# Sensors.net
KiCad netlist of a schematic drawn in Altium Designer
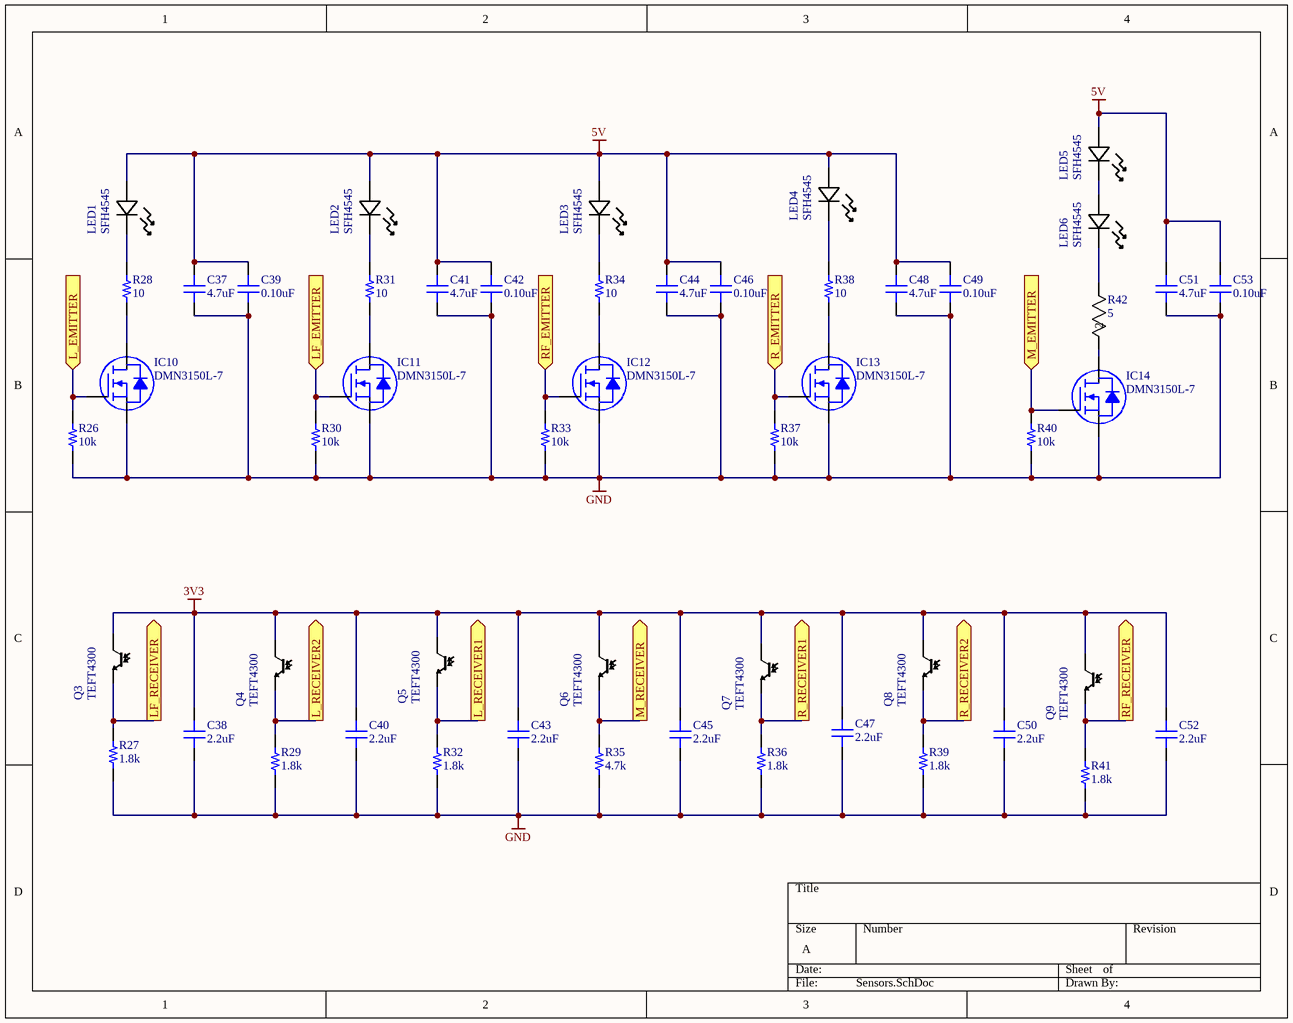
[diagram p0: Sensors.SchDoc]

(export (version "E")
  (design (tool "Eeschema 10.0.6"))
  (components
    (comp (ref "C37")
      (value "4.7uF")
      (footprint "CAP 0805/2012")
      (description "CAP CER 4.7UF 10V Y5V 0805")
      (fields (field (name "PART NUMBER") "CC0805ZRY5V6BB475") (field (name "MANUFACTURER") "Yageo"))
      (libsource (lib "Celestial Library Database") (part "Capacitor"))
    )
    (comp (ref "C38")
      (value "2.2uF")
      (footprint "CAP 0402/1005")
      (description "CAP CER 2.2UF 10V X5R 0402")
      (fields
        (field (name "PART NUMBER") "CL05A225KP5NSNC")
        (field (name "MANUFACTURER") "Samsung Electro-Mechanics America, Inc.")
      )
      (libsource (lib "Celestial Library Database") (part "Capacitor"))
    )
    (comp (ref "C39")
      (value "0.10uF")
      (footprint "CAP 0603/1608")
      (description "CAP CER 0.1UF 25V Y5V 0603")
      (fields (field (name "PART NUMBER") "CC0603ZRY5V8BB104") (field (name "MANUFACTURER") "Yageo"))
      (libsource (lib "Celestial Library Database") (part "Capacitor"))
    )
    (comp (ref "C40")
      (value "2.2uF")
      (footprint "CAP 0402/1005")
      (description "CAP CER 2.2UF 10V X5R 0402")
      (fields
        (field (name "PART NUMBER") "CL05A225KP5NSNC")
        (field (name "MANUFACTURER") "Samsung Electro-Mechanics America, Inc.")
      )
      (libsource (lib "Celestial Library Database") (part "Capacitor"))
    )
    (comp (ref "C41")
      (value "4.7uF")
      (footprint "CAP 0805/2012")
      (description "CAP CER 4.7UF 10V Y5V 0805")
      (fields (field (name "PART NUMBER") "CC0805ZRY5V6BB475") (field (name "MANUFACTURER") "Yageo"))
      (libsource (lib "Celestial Library Database") (part "Capacitor"))
    )
    (comp (ref "C42")
      (value "0.10uF")
      (footprint "CAP 0603/1608")
      (description "CAP CER 0.1UF 25V Y5V 0603")
      (fields (field (name "PART NUMBER") "CC0603ZRY5V8BB104") (field (name "MANUFACTURER") "Yageo"))
      (libsource (lib "Celestial Library Database") (part "Capacitor"))
    )
    (comp (ref "C43")
      (value "2.2uF")
      (footprint "CAP 0402/1005")
      (description "CAP CER 2.2UF 10V X5R 0402")
      (fields
        (field (name "PART NUMBER") "CL05A225KP5NSNC")
        (field (name "MANUFACTURER") "Samsung Electro-Mechanics America, Inc.")
      )
      (libsource (lib "Celestial Library Database") (part "Capacitor"))
    )
    (comp (ref "C44")
      (value "4.7uF")
      (footprint "CAP 0805/2012")
      (description "CAP CER 4.7UF 10V Y5V 0805")
      (fields (field (name "PART NUMBER") "CC0805ZRY5V6BB475") (field (name "MANUFACTURER") "Yageo"))
      (libsource (lib "Celestial Library Database") (part "Capacitor"))
    )
    (comp (ref "C45")
      (value "2.2uF")
      (footprint "CAP 0402/1005")
      (description "CAP CER 2.2UF 10V X5R 0402")
      (fields
        (field (name "PART NUMBER") "CL05A225KP5NSNC")
        (field (name "MANUFACTURER") "Samsung Electro-Mechanics America, Inc.")
      )
      (libsource (lib "Celestial Library Database") (part "Capacitor"))
    )
    (comp (ref "C46")
      (value "0.10uF")
      (footprint "CAP 0603/1608")
      (description "CAP CER 0.1UF 25V Y5V 0603")
      (fields (field (name "PART NUMBER") "CC0603ZRY5V8BB104") (field (name "MANUFACTURER") "Yageo"))
      (libsource (lib "Celestial Library Database") (part "Capacitor"))
    )
    (comp (ref "C47")
      (value "2.2uF")
      (footprint "CAP 0402/1005")
      (description "CAP CER 2.2UF 10V X5R 0402")
      (fields
        (field (name "PART NUMBER") "CL05A225KP5NSNC")
        (field (name "MANUFACTURER") "Samsung Electro-Mechanics America, Inc.")
      )
      (libsource (lib "Celestial Library Database") (part "Capacitor"))
    )
    (comp (ref "C48")
      (value "4.7uF")
      (footprint "CAP 0805/2012")
      (description "CAP CER 4.7UF 10V Y5V 0805")
      (fields (field (name "PART NUMBER") "CC0805ZRY5V6BB475") (field (name "MANUFACTURER") "Yageo"))
      (libsource (lib "Celestial Library Database") (part "Capacitor"))
    )
    (comp (ref "C49")
      (value "0.10uF")
      (footprint "CAP 0603/1608")
      (description "CAP CER 0.1UF 25V Y5V 0603")
      (fields (field (name "PART NUMBER") "CC0603ZRY5V8BB104") (field (name "MANUFACTURER") "Yageo"))
      (libsource (lib "Celestial Library Database") (part "Capacitor"))
    )
    (comp (ref "C50")
      (value "2.2uF")
      (footprint "CAP 0402/1005")
      (description "CAP CER 2.2UF 10V X5R 0402")
      (fields
        (field (name "PART NUMBER") "CL05A225KP5NSNC")
        (field (name "MANUFACTURER") "Samsung Electro-Mechanics America, Inc.")
      )
      (libsource (lib "Celestial Library Database") (part "Capacitor"))
    )
    (comp (ref "C51")
      (value "4.7uF")
      (footprint "CAP 0805/2012")
      (description "CAP CER 4.7UF 10V Y5V 0805")
      (fields (field (name "PART NUMBER") "CC0805ZRY5V6BB475") (field (name "MANUFACTURER") "Yageo"))
      (libsource (lib "Celestial Library Database") (part "Capacitor"))
    )
    (comp (ref "C52")
      (value "2.2uF")
      (footprint "CAP 0402/1005")
      (description "CAP CER 2.2UF 10V X5R 0402")
      (fields
        (field (name "PART NUMBER") "CL05A225KP5NSNC")
        (field (name "MANUFACTURER") "Samsung Electro-Mechanics America, Inc.")
      )
      (libsource (lib "Celestial Library Database") (part "Capacitor"))
    )
    (comp (ref "C53")
      (value "0.10uF")
      (footprint "CAP 0603/1608")
      (description "CAP CER 0.1UF 25V Y5V 0603")
      (fields (field (name "PART NUMBER") "CC0603ZRY5V8BB104") (field (name "MANUFACTURER") "Yageo"))
      (libsource (lib "Celestial Library Database") (part "Capacitor"))
    )
    (comp (ref "IC10")
      (value "DMN3150L-7")
      (footprint "DIODES SOT-23-3")
      (description "MOSFET N-CH 28V 3.2A SOT23-3")
      (fields (field (name "MANUFACTURER") "Diodes Incorporated"))
      (libsource (lib "Celestial Library Database") (part "DIODES INC MOSFET N-CH SOT-23-3"))
    )
    (comp (ref "IC11")
      (value "DMN3150L-7")
      (footprint "DIODES SOT-23-3")
      (description "MOSFET N-CH 28V 3.2A SOT23-3")
      (fields (field (name "MANUFACTURER") "Diodes Incorporated"))
      (libsource (lib "Celestial Library Database") (part "DIODES INC MOSFET N-CH SOT-23-3"))
    )
    (comp (ref "IC12")
      (value "DMN3150L-7")
      (footprint "DIODES SOT-23-3")
      (description "MOSFET N-CH 28V 3.2A SOT23-3")
      (fields (field (name "MANUFACTURER") "Diodes Incorporated"))
      (libsource (lib "Celestial Library Database") (part "DIODES INC MOSFET N-CH SOT-23-3"))
    )
    (comp (ref "IC13")
      (value "DMN3150L-7")
      (footprint "DIODES SOT-23-3")
      (description "MOSFET N-CH 28V 3.2A SOT23-3")
      (fields (field (name "MANUFACTURER") "Diodes Incorporated"))
      (libsource (lib "Celestial Library Database") (part "DIODES INC MOSFET N-CH SOT-23-3"))
    )
    (comp (ref "IC14")
      (value "DMN3150L-7")
      (footprint "DIODES SOT-23-3")
      (description "MOSFET N-CH 28V 3.2A SOT23-3")
      (fields (field (name "MANUFACTURER") "Diodes Incorporated"))
      (libsource (lib "Celestial Library Database") (part "DIODES INC MOSFET N-CH SOT-23-3"))
    )
    (comp (ref "LED1")
      (value "SFH4545")
      (footprint "LED_TLH")
      (description "Imported")
      (libsource (lib "AltiumDesigner") (part "SFH4545"))
    )
    (comp (ref "LED2")
      (value "SFH4545")
      (footprint "LED_TLH")
      (description "Imported")
      (libsource (lib "AltiumDesigner") (part "SFH4545"))
    )
    (comp (ref "LED3")
      (value "SFH4545")
      (footprint "LED_TLH")
      (description "Imported")
      (libsource (lib "AltiumDesigner") (part "SFH4545"))
    )
    (comp (ref "LED4")
      (value "SFH4545")
      (footprint "LED_TLH")
      (description "Imported")
      (libsource (lib "AltiumDesigner") (part "SFH4545"))
    )
    (comp (ref "LED5")
      (value "SFH4545")
      (footprint "LED_TLH")
      (description "Imported")
      (libsource (lib "AltiumDesigner") (part "SFH4545"))
    )
    (comp (ref "LED6")
      (value "SFH4545")
      (footprint "LED_TLH")
      (description "Imported")
      (libsource (lib "AltiumDesigner") (part "SFH4545"))
    )
    (comp (ref "Q3")
      (value "TEFT4300")
      (footprint "LED_TLH")
      (description "Imported")
      (libsource (lib "AltiumDesigner") (part "TEFT4300"))
    )
    (comp (ref "Q4")
      (value "TEFT4300")
      (footprint "LED_TLH")
      (description "Imported")
      (libsource (lib "AltiumDesigner") (part "TEFT4300"))
    )
    (comp (ref "Q5")
      (value "TEFT4300")
      (footprint "LED_TLH")
      (description "Imported")
      (libsource (lib "AltiumDesigner") (part "TEFT4300"))
    )
    (comp (ref "Q6")
      (value "TEFT4300")
      (footprint "LED_TLH")
      (description "Imported")
      (libsource (lib "AltiumDesigner") (part "TEFT4300"))
    )
    (comp (ref "Q7")
      (value "TEFT4300")
      (footprint "LED_TLH")
      (description "Imported")
      (libsource (lib "AltiumDesigner") (part "TEFT4300"))
    )
    (comp (ref "Q8")
      (value "TEFT4300")
      (footprint "LED_TLH")
      (description "Imported")
      (libsource (lib "AltiumDesigner") (part "TEFT4300"))
    )
    (comp (ref "Q9")
      (value "TEFT4300")
      (footprint "LED_TLH")
      (description "Imported")
      (libsource (lib "AltiumDesigner") (part "TEFT4300"))
    )
    (comp (ref "R26")
      (value "10k")
      (footprint "RES 0402/1005")
      (description "RES SMD 10K OHM 5% 1/16W 0402")
      (fields (field (name "PART NUMBER") "RC0402JR-0710KL") (field (name "MANUFACTURER") "Yageo"))
      (libsource (lib "Celestial Library Database") (part "Resistor"))
    )
    (comp (ref "R27")
      (value "1.8k")
      (footprint "RES 0402/1005")
      (description "RES SMD 1.8K OHM 5% 1/16W 0402")
      (fields (field (name "PART NUMBER") "RC0402JR-071K8L") (field (name "MANUFACTURER") "Yageo"))
      (libsource (lib "Celestial Library Database") (part "Resistor"))
    )
    (comp (ref "R28")
      (value "10")
      (footprint "RES 0603/1608")
      (description "RES SMD 4.7K OHM 1% 1/10W 0603")
      (fields (field (name "PART NUMBER") "RK73B1JTTDD100J") (field (name "TOLERANCE") "1%"))
      (libsource (lib "Celestial Library Database") (part "Resistor"))
    )
    (comp (ref "R29")
      (value "1.8k")
      (footprint "RES 0402/1005")
      (description "RES SMD 1.8K OHM 5% 1/16W 0402")
      (fields (field (name "PART NUMBER") "RC0402JR-071K8L") (field (name "MANUFACTURER") "Yageo"))
      (libsource (lib "Celestial Library Database") (part "Resistor"))
    )
    (comp (ref "R30")
      (value "10k")
      (footprint "RES 0402/1005")
      (description "RES SMD 10K OHM 5% 1/16W 0402")
      (fields (field (name "PART NUMBER") "RC0402JR-0710KL") (field (name "MANUFACTURER") "Yageo"))
      (libsource (lib "Celestial Library Database") (part "Resistor"))
    )
    (comp (ref "R31")
      (value "10")
      (footprint "RES 0603/1608")
      (description "RES SMD 4.7K OHM 1% 1/10W 0603")
      (fields (field (name "PART NUMBER") "RK73B1JTTDD100J") (field (name "TOLERANCE") "1%"))
      (libsource (lib "Celestial Library Database") (part "Resistor"))
    )
    (comp (ref "R32")
      (value "1.8k")
      (footprint "RES 0402/1005")
      (description "RES SMD 1.8K OHM 5% 1/16W 0402")
      (fields (field (name "PART NUMBER") "RC0402JR-071K8L") (field (name "MANUFACTURER") "Yageo"))
      (libsource (lib "Celestial Library Database") (part "Resistor"))
    )
    (comp (ref "R33")
      (value "10k")
      (footprint "RES 0402/1005")
      (description "RES SMD 10K OHM 5% 1/16W 0402")
      (fields (field (name "PART NUMBER") "RC0402JR-0710KL") (field (name "MANUFACTURER") "Yageo"))
      (libsource (lib "Celestial Library Database") (part "Resistor"))
    )
    (comp (ref "R34")
      (value "10")
      (footprint "RES 0603/1608")
      (description "RES SMD 4.7K OHM 1% 1/10W 0603")
      (fields (field (name "PART NUMBER") "RK73B1JTTDD100J") (field (name "TOLERANCE") "1%"))
      (libsource (lib "Celestial Library Database") (part "Resistor"))
    )
    (comp (ref "R35")
      (value "4.7k")
      (footprint "RES 0402/1005")
      (description "RES SMD 4.7K OHM 5% 1/16W 0402")
      (fields (field (name "PART NUMBER") "RC0402JR-074K7L") (field (name "MANUFACTURER") "Yageo"))
      (libsource (lib "Celestial Library Database") (part "Resistor"))
    )
    (comp (ref "R36")
      (value "1.8k")
      (footprint "RES 0402/1005")
      (description "RES SMD 1.8K OHM 5% 1/16W 0402")
      (fields (field (name "PART NUMBER") "RC0402JR-071K8L") (field (name "MANUFACTURER") "Yageo"))
      (libsource (lib "Celestial Library Database") (part "Resistor"))
    )
    (comp (ref "R37")
      (value "10k")
      (footprint "RES 0402/1005")
      (description "RES SMD 10K OHM 5% 1/16W 0402")
      (fields (field (name "PART NUMBER") "RC0402JR-0710KL") (field (name "MANUFACTURER") "Yageo"))
      (libsource (lib "Celestial Library Database") (part "Resistor"))
    )
    (comp (ref "R38")
      (value "10")
      (footprint "RES 0603/1608")
      (description "RES SMD 4.7K OHM 1% 1/10W 0603")
      (fields (field (name "PART NUMBER") "RK73B1JTTDD100J") (field (name "TOLERANCE") "1%"))
      (libsource (lib "Celestial Library Database") (part "Resistor"))
    )
    (comp (ref "R39")
      (value "1.8k")
      (footprint "RES 0402/1005")
      (description "RES SMD 1.8K OHM 5% 1/16W 0402")
      (fields (field (name "PART NUMBER") "RC0402JR-071K8L") (field (name "MANUFACTURER") "Yageo"))
      (libsource (lib "Celestial Library Database") (part "Resistor"))
    )
    (comp (ref "R40")
      (value "10k")
      (footprint "RES 0402/1005")
      (description "RES SMD 10K OHM 5% 1/16W 0402")
      (fields (field (name "PART NUMBER") "RC0402JR-0710KL") (field (name "MANUFACTURER") "Yageo"))
      (libsource (lib "Celestial Library Database") (part "Resistor"))
    )
    (comp (ref "R41")
      (value "1.8k")
      (footprint "RES 0402/1005")
      (description "RES SMD 1.8K OHM 5% 1/16W 0402")
      (fields (field (name "PART NUMBER") "RC0402JR-071K8L") (field (name "MANUFACTURER") "Yageo"))
      (libsource (lib "Celestial Library Database") (part "Resistor"))
    )
    (comp (ref "R42")
      (value "5")
      (footprint "RES_WSC_2515")
      (description "No Description Available")
      (fields
        (field (name "MANUFACTURER_PART_NUMBER") "WSC25155R000FEA")
        (field (name "COPYRIGHT") "Copyright (C) 2018 Accelerated Designs. All rights reserved")
      )
      (libsource (lib "WSC25155R000FEA") (part "WSC25155R000FEA"))
    )
  )
  (nets
    (net (code "1") (name "/LF_EMITTER") (class "Default")
      (node (ref "IC11") (pin "1") (pinfunction "G_1") (pintype "passive"))
      (node (ref "R30") (pin "2") (pinfunction "2_2") (pintype "passive"))
    )
    (net (code "2") (name "/LF_RECEIVER") (class "Default")
      (node (ref "Q3") (pin "1") (pinfunction "1_1") (pintype "passive"))
      (node (ref "R27") (pin "2") (pinfunction "2_2") (pintype "passive"))
    )
    (net (code "3") (name "/L_EMITTER") (class "Default")
      (node (ref "IC10") (pin "1") (pinfunction "G_1") (pintype "passive"))
      (node (ref "R26") (pin "2") (pinfunction "2_2") (pintype "passive"))
    )
    (net (code "4") (name "/L_RECEIVER1") (class "Default")
      (node (ref "Q5") (pin "1") (pinfunction "1_1") (pintype "passive"))
      (node (ref "R32") (pin "2") (pinfunction "2_2") (pintype "passive"))
    )
    (net (code "5") (name "/L_RECEIVER2") (class "Default")
      (node (ref "Q4") (pin "1") (pinfunction "1_1") (pintype "passive"))
      (node (ref "R29") (pin "2") (pinfunction "2_2") (pintype "passive"))
    )
    (net (code "6") (name "/M_EMITTER") (class "Default")
      (node (ref "IC14") (pin "1") (pinfunction "G_1") (pintype "passive"))
      (node (ref "R40") (pin "2") (pinfunction "2_2") (pintype "passive"))
    )
    (net (code "7") (name "/M_RECEIVER") (class "Default")
      (node (ref "Q6") (pin "1") (pinfunction "1_1") (pintype "passive"))
      (node (ref "R35") (pin "2") (pinfunction "2_2") (pintype "passive"))
    )
    (net (code "8") (name "/RF_EMITTER") (class "Default")
      (node (ref "IC12") (pin "1") (pinfunction "G_1") (pintype "passive"))
      (node (ref "R33") (pin "2") (pinfunction "2_2") (pintype "passive"))
    )
    (net (code "9") (name "/RF_RECEIVER") (class "Default")
      (node (ref "Q9") (pin "1") (pinfunction "1_1") (pintype "passive"))
      (node (ref "R41") (pin "2") (pinfunction "2_2") (pintype "passive"))
    )
    (net (code "10") (name "/R_EMITTER") (class "Default")
      (node (ref "IC13") (pin "1") (pinfunction "G_1") (pintype "passive"))
      (node (ref "R37") (pin "2") (pinfunction "2_2") (pintype "passive"))
    )
    (net (code "11") (name "/R_RECEIVER1") (class "Default")
      (node (ref "Q7") (pin "1") (pinfunction "1_1") (pintype "passive"))
      (node (ref "R36") (pin "2") (pinfunction "2_2") (pintype "passive"))
    )
    (net (code "12") (name "/R_RECEIVER2") (class "Default")
      (node (ref "Q8") (pin "1") (pinfunction "1_1") (pintype "passive"))
      (node (ref "R39") (pin "2") (pinfunction "2_2") (pintype "passive"))
    )
    (net (code "13") (name "3V3") (class "Default")
      (node (ref "C38") (pin "1") (pinfunction "1_1") (pintype "passive"))
      (node (ref "C40") (pin "1") (pinfunction "1_1") (pintype "passive"))
      (node (ref "C43") (pin "1") (pinfunction "1_1") (pintype "passive"))
      (node (ref "C45") (pin "1") (pinfunction "1_1") (pintype "passive"))
      (node (ref "C47") (pin "1") (pinfunction "1_1") (pintype "passive"))
      (node (ref "C50") (pin "1") (pinfunction "1_1") (pintype "passive"))
      (node (ref "C52") (pin "1") (pinfunction "1_1") (pintype "passive"))
      (node (ref "Q3") (pin "2") (pinfunction "2_2") (pintype "passive"))
      (node (ref "Q4") (pin "2") (pinfunction "2_2") (pintype "passive"))
      (node (ref "Q5") (pin "2") (pinfunction "2_2") (pintype "passive"))
      (node (ref "Q6") (pin "2") (pinfunction "2_2") (pintype "passive"))
      (node (ref "Q7") (pin "2") (pinfunction "2_2") (pintype "passive"))
      (node (ref "Q8") (pin "2") (pinfunction "2_2") (pintype "passive"))
      (node (ref "Q9") (pin "2") (pinfunction "2_2") (pintype "passive"))
    )
    (net (code "14") (name "5V") (class "Default")
      (node (ref "C37") (pin "2") (pinfunction "2_2") (pintype "passive"))
      (node (ref "C39") (pin "2") (pinfunction "2_2") (pintype "passive"))
      (node (ref "C41") (pin "2") (pinfunction "2_2") (pintype "passive"))
      (node (ref "C42") (pin "2") (pinfunction "2_2") (pintype "passive"))
      (node (ref "C44") (pin "2") (pinfunction "2_2") (pintype "passive"))
      (node (ref "C46") (pin "2") (pinfunction "2_2") (pintype "passive"))
      (node (ref "C48") (pin "2") (pinfunction "2_2") (pintype "passive"))
      (node (ref "C49") (pin "2") (pinfunction "2_2") (pintype "passive"))
      (node (ref "C51") (pin "2") (pinfunction "2_2") (pintype "passive"))
      (node (ref "C53") (pin "2") (pinfunction "2_2") (pintype "passive"))
      (node (ref "LED1") (pin "2") (pinfunction "2_2") (pintype "passive"))
      (node (ref "LED2") (pin "2") (pinfunction "2_2") (pintype "passive"))
      (node (ref "LED3") (pin "2") (pinfunction "2_2") (pintype "passive"))
      (node (ref "LED4") (pin "2") (pinfunction "2_2") (pintype "passive"))
      (node (ref "LED5") (pin "2") (pinfunction "2_2") (pintype "passive"))
    )
    (net (code "15") (name "GND") (class "Default")
      (node (ref "C37") (pin "1") (pinfunction "1_1") (pintype "passive"))
      (node (ref "C38") (pin "2") (pinfunction "2_2") (pintype "passive"))
      (node (ref "C39") (pin "1") (pinfunction "1_1") (pintype "passive"))
      (node (ref "C40") (pin "2") (pinfunction "2_2") (pintype "passive"))
      (node (ref "C41") (pin "1") (pinfunction "1_1") (pintype "passive"))
      (node (ref "C42") (pin "1") (pinfunction "1_1") (pintype "passive"))
      (node (ref "C43") (pin "2") (pinfunction "2_2") (pintype "passive"))
      (node (ref "C44") (pin "1") (pinfunction "1_1") (pintype "passive"))
      (node (ref "C45") (pin "2") (pinfunction "2_2") (pintype "passive"))
      (node (ref "C46") (pin "1") (pinfunction "1_1") (pintype "passive"))
      (node (ref "C47") (pin "2") (pinfunction "2_2") (pintype "passive"))
      (node (ref "C48") (pin "1") (pinfunction "1_1") (pintype "passive"))
      (node (ref "C49") (pin "1") (pinfunction "1_1") (pintype "passive"))
      (node (ref "C50") (pin "2") (pinfunction "2_2") (pintype "passive"))
      (node (ref "C51") (pin "1") (pinfunction "1_1") (pintype "passive"))
      (node (ref "C52") (pin "2") (pinfunction "2_2") (pintype "passive"))
      (node (ref "C53") (pin "1") (pinfunction "1_1") (pintype "passive"))
      (node (ref "IC10") (pin "3") (pinfunction "S_3") (pintype "passive"))
      (node (ref "IC11") (pin "3") (pinfunction "S_3") (pintype "passive"))
      (node (ref "IC12") (pin "3") (pinfunction "S_3") (pintype "passive"))
      (node (ref "IC13") (pin "3") (pinfunction "S_3") (pintype "passive"))
      (node (ref "IC14") (pin "3") (pinfunction "S_3") (pintype "passive"))
      (node (ref "R26") (pin "1") (pinfunction "1_1") (pintype "passive"))
      (node (ref "R27") (pin "1") (pinfunction "1_1") (pintype "passive"))
      (node (ref "R29") (pin "1") (pinfunction "1_1") (pintype "passive"))
      (node (ref "R30") (pin "1") (pinfunction "1_1") (pintype "passive"))
      (node (ref "R32") (pin "1") (pinfunction "1_1") (pintype "passive"))
      (node (ref "R33") (pin "1") (pinfunction "1_1") (pintype "passive"))
      (node (ref "R35") (pin "1") (pinfunction "1_1") (pintype "passive"))
      (node (ref "R36") (pin "1") (pinfunction "1_1") (pintype "passive"))
      (node (ref "R37") (pin "1") (pinfunction "1_1") (pintype "passive"))
      (node (ref "R39") (pin "1") (pinfunction "1_1") (pintype "passive"))
      (node (ref "R40") (pin "1") (pinfunction "1_1") (pintype "passive"))
      (node (ref "R41") (pin "1") (pinfunction "1_1") (pintype "passive"))
    )
    (net (code "16") (name "Net-(IC10-D)") (class "Default")
      (node (ref "IC10") (pin "2") (pinfunction "D_2") (pintype "passive"))
      (node (ref "R28") (pin "2") (pinfunction "2_2") (pintype "passive"))
    )
    (net (code "17") (name "Net-(IC11-D)") (class "Default")
      (node (ref "IC11") (pin "2") (pinfunction "D_2") (pintype "passive"))
      (node (ref "R31") (pin "2") (pinfunction "2_2") (pintype "passive"))
    )
    (net (code "18") (name "Net-(IC12-D)") (class "Default")
      (node (ref "IC12") (pin "2") (pinfunction "D_2") (pintype "passive"))
      (node (ref "R34") (pin "2") (pinfunction "2_2") (pintype "passive"))
    )
    (net (code "19") (name "Net-(IC13-D)") (class "Default")
      (node (ref "IC13") (pin "2") (pinfunction "D_2") (pintype "passive"))
      (node (ref "R38") (pin "2") (pinfunction "2_2") (pintype "passive"))
    )
    (net (code "20") (name "Net-(IC14-D)") (class "Default")
      (node (ref "IC14") (pin "2") (pinfunction "D_2") (pintype "passive"))
      (node (ref "R42") (pin "2") (pinfunction "2_2") (pintype "passive"))
    )
    (net (code "21") (name "Net-(LED1-Pad1)") (class "Default")
      (node (ref "LED1") (pin "1") (pinfunction "1_1") (pintype "passive"))
      (node (ref "R28") (pin "1") (pinfunction "1_1") (pintype "passive"))
    )
    (net (code "22") (name "Net-(LED2-Pad1)") (class "Default")
      (node (ref "LED2") (pin "1") (pinfunction "1_1") (pintype "passive"))
      (node (ref "R31") (pin "1") (pinfunction "1_1") (pintype "passive"))
    )
    (net (code "23") (name "Net-(LED3-Pad1)") (class "Default")
      (node (ref "LED3") (pin "1") (pinfunction "1_1") (pintype "passive"))
      (node (ref "R34") (pin "1") (pinfunction "1_1") (pintype "passive"))
    )
    (net (code "24") (name "Net-(LED4-Pad1)") (class "Default")
      (node (ref "LED4") (pin "1") (pinfunction "1_1") (pintype "passive"))
      (node (ref "R38") (pin "1") (pinfunction "1_1") (pintype "passive"))
    )
    (net (code "25") (name "Net-(LED5-Pad1)") (class "Default")
      (node (ref "LED5") (pin "1") (pinfunction "1_1") (pintype "passive"))
      (node (ref "LED6") (pin "2") (pinfunction "2_2") (pintype "passive"))
    )
    (net (code "26") (name "Net-(LED6-Pad1)") (class "Default")
      (node (ref "LED6") (pin "1") (pinfunction "1_1") (pintype "passive"))
      (node (ref "R42") (pin "1") (pinfunction "1_1") (pintype "passive"))
    )
  )
)
